# current-amplifier.net
KiCad netlist of a schematic drawn in EAGLE
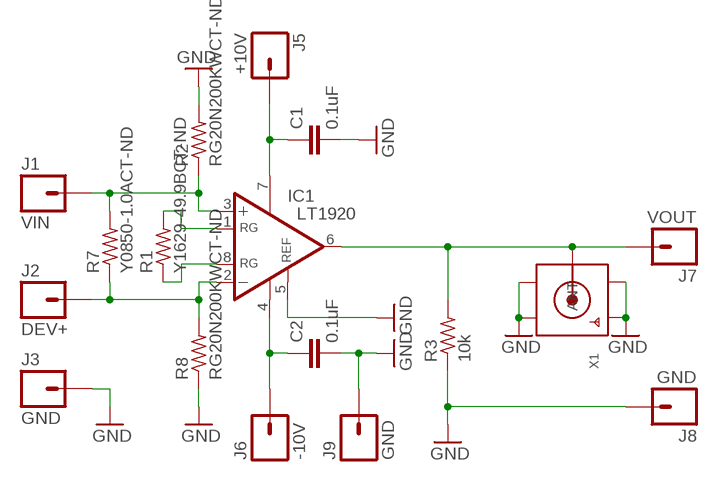
[diagram p0: schematic, sheet 1]

(export (version "E")
  (design (tool "Eeschema 10.0.6"))
  (components
    (comp (ref "C1")
      (value "0.1uF")
      (footprint "eagle-import:C0805")
      (libsource (lib "eagle-import") (part "C-EUC0805"))
    )
    (comp (ref "C2")
      (value "0.1uF")
      (footprint "eagle-import:C0805")
      (libsource (lib "eagle-import") (part "C-EUC0805"))
    )
    (comp (ref "IC1")
      (value "LT1920")
      (footprint "eagle-import:SOIC8")
      (fields (field (name "MPN") "LT1168IS8"))
      (libsource (lib "eagle-import") (part "LT1168S8I"))
    )
    (comp (ref "J1")
      (value "VIN")
      (footprint "eagle-import:1X01")
      (libsource (lib "eagle-import") (part "M01PTH"))
    )
    (comp (ref "J2")
      (value "DEV+")
      (footprint "eagle-import:1X01")
      (libsource (lib "eagle-import") (part "M01PTH"))
    )
    (comp (ref "J3")
      (value "GND")
      (footprint "eagle-import:1X01")
      (libsource (lib "eagle-import") (part "M01PTH"))
    )
    (comp (ref "J5")
      (value "+10V")
      (footprint "eagle-import:1X01")
      (libsource (lib "eagle-import") (part "M01PTH"))
    )
    (comp (ref "J6")
      (value "-10V")
      (footprint "eagle-import:1X01")
      (libsource (lib "eagle-import") (part "M01PTH"))
    )
    (comp (ref "J7")
      (value "VOUT")
      (footprint "eagle-import:1X01")
      (libsource (lib "eagle-import") (part "M01PTH"))
    )
    (comp (ref "J8")
      (value "GND")
      (footprint "eagle-import:1X01")
      (libsource (lib "eagle-import") (part "M01PTH"))
    )
    (comp (ref "J9")
      (value "GND")
      (footprint "eagle-import:1X01")
      (libsource (lib "eagle-import") (part "M01PTH"))
    )
    (comp (ref "R1")
      (value "Y1629-49.9BCT-ND")
      (footprint "eagle-import:R0805")
      (libsource (lib "eagle-import") (part "resistor_R-US_R0805"))
    )
    (comp (ref "R2")
      (value "RG20N200KWCT-ND")
      (footprint "eagle-import:R0805")
      (libsource (lib "eagle-import") (part "resistor_R-US_R0805"))
    )
    (comp (ref "R3")
      (value "10k")
      (footprint "eagle-import:R0805")
      (libsource (lib "eagle-import") (part "resistor_R-US_R0805"))
    )
    (comp (ref "R7")
      (value "Y0850-1.0ACT-ND")
      (footprint "eagle-import:R2516WIDE")
      (libsource (lib "eagle-import") (part "R-US_R2516WIDE"))
    )
    (comp (ref "R8")
      (value "RG20N200KWCT-ND")
      (footprint "eagle-import:R0805")
      (libsource (lib "eagle-import") (part "resistor_R-US_R0805"))
    )
    (comp (ref "X1")
      (value "SMACONNECTOR_EDGE")
      (footprint "eagle-import:SMA_EDGELAUNCH")
      (libsource (lib "eagle-import") (part "SMACONNECTOR_EDGE"))
    )
  )
  (nets
    (net (code "1") (name "GND") (class "Default")
      (node (ref "C1") (pin "2") (pinfunction "2_2") (pintype "passive"))
      (node (ref "C2") (pin "2") (pinfunction "2_2") (pintype "passive"))
      (node (ref "IC1") (pin "5") (pinfunction "REF_5") (pintype "input"))
      (node (ref "J3") (pin "1") (pinfunction "1_1") (pintype "passive"))
      (node (ref "J8") (pin "1") (pinfunction "1_1") (pintype "passive"))
      (node (ref "J9") (pin "1") (pinfunction "1_1") (pintype "passive"))
      (node (ref "R2") (pin "2") (pinfunction "2_2") (pintype "passive"))
      (node (ref "R3") (pin "1") (pinfunction "1_1") (pintype "passive"))
      (node (ref "R8") (pin "1") (pinfunction "1_1") (pintype "passive"))
      (node (ref "X1") (pin "GND@1") (pinfunction "GND4_GND@1") (pintype "power_in"))
      (node (ref "X1") (pin "GND@2") (pinfunction "GND3_GND@2") (pintype "power_in"))
      (node (ref "X1") (pin "GND@3") (pinfunction "GND2_GND@3") (pintype "power_in"))
      (node (ref "X1") (pin "GND@4") (pinfunction "GND1_GND@4") (pintype "power_in"))
    )
    (net (code "2") (name "Net-(IC1-+IN)") (class "Default")
      (node (ref "IC1") (pin "3") (pinfunction "+IN_3") (pintype "input"))
      (node (ref "J1") (pin "1") (pinfunction "1_1") (pintype "passive"))
      (node (ref "R2") (pin "1") (pinfunction "1_1") (pintype "passive"))
      (node (ref "R7") (pin "B1") (pinfunction "2_B1") (pintype "passive"))
      (node (ref "R7") (pin "B2") (pinfunction "2_B2") (pintype "passive"))
    )
    (net (code "3") (name "Net-(IC1--IN)") (class "Default")
      (node (ref "IC1") (pin "2") (pinfunction "-IN_2") (pintype "input"))
      (node (ref "J2") (pin "1") (pinfunction "1_1") (pintype "passive"))
      (node (ref "R7") (pin "A1") (pinfunction "1_A1") (pintype "passive"))
      (node (ref "R7") (pin "A2") (pinfunction "1_A2") (pintype "passive"))
      (node (ref "R8") (pin "2") (pinfunction "2_2") (pintype "passive"))
    )
    (net (code "4") (name "Net-(IC1-OUT)") (class "Default")
      (node (ref "IC1") (pin "6") (pinfunction "OUT_6") (pintype "output"))
      (node (ref "J7") (pin "1") (pinfunction "1_1") (pintype "passive"))
      (node (ref "R3") (pin "2") (pinfunction "2_2") (pintype "passive"))
      (node (ref "X1") (pin "P") (pinfunction "ANT_P") (pintype "bidirectional"))
    )
    (net (code "5") (name "Net-(IC1-RG-Pad1)") (class "Default")
      (node (ref "IC1") (pin "1") (pinfunction "RG_1") (pintype "input"))
      (node (ref "R1") (pin "2") (pinfunction "2_2") (pintype "passive"))
    )
    (net (code "6") (name "Net-(IC1-RG-Pad8)") (class "Default")
      (node (ref "IC1") (pin "8") (pinfunction "RG_8") (pintype "input"))
      (node (ref "R1") (pin "1") (pinfunction "1_1") (pintype "passive"))
    )
    (net (code "7") (name "Net-(IC1-V+)") (class "Default")
      (node (ref "C1") (pin "1") (pinfunction "1_1") (pintype "passive"))
      (node (ref "IC1") (pin "7") (pinfunction "V+_7") (pintype "power_in"))
      (node (ref "J5") (pin "1") (pinfunction "1_1") (pintype "passive"))
    )
    (net (code "8") (name "Net-(IC1-V-)") (class "Default")
      (node (ref "C2") (pin "1") (pinfunction "1_1") (pintype "passive"))
      (node (ref "IC1") (pin "4") (pinfunction "V-_4") (pintype "power_in"))
      (node (ref "J6") (pin "1") (pinfunction "1_1") (pintype "passive"))
    )
  )
)
